# DIFFAMP.net
KiCad netlist of a schematic drawn in Altium Designer
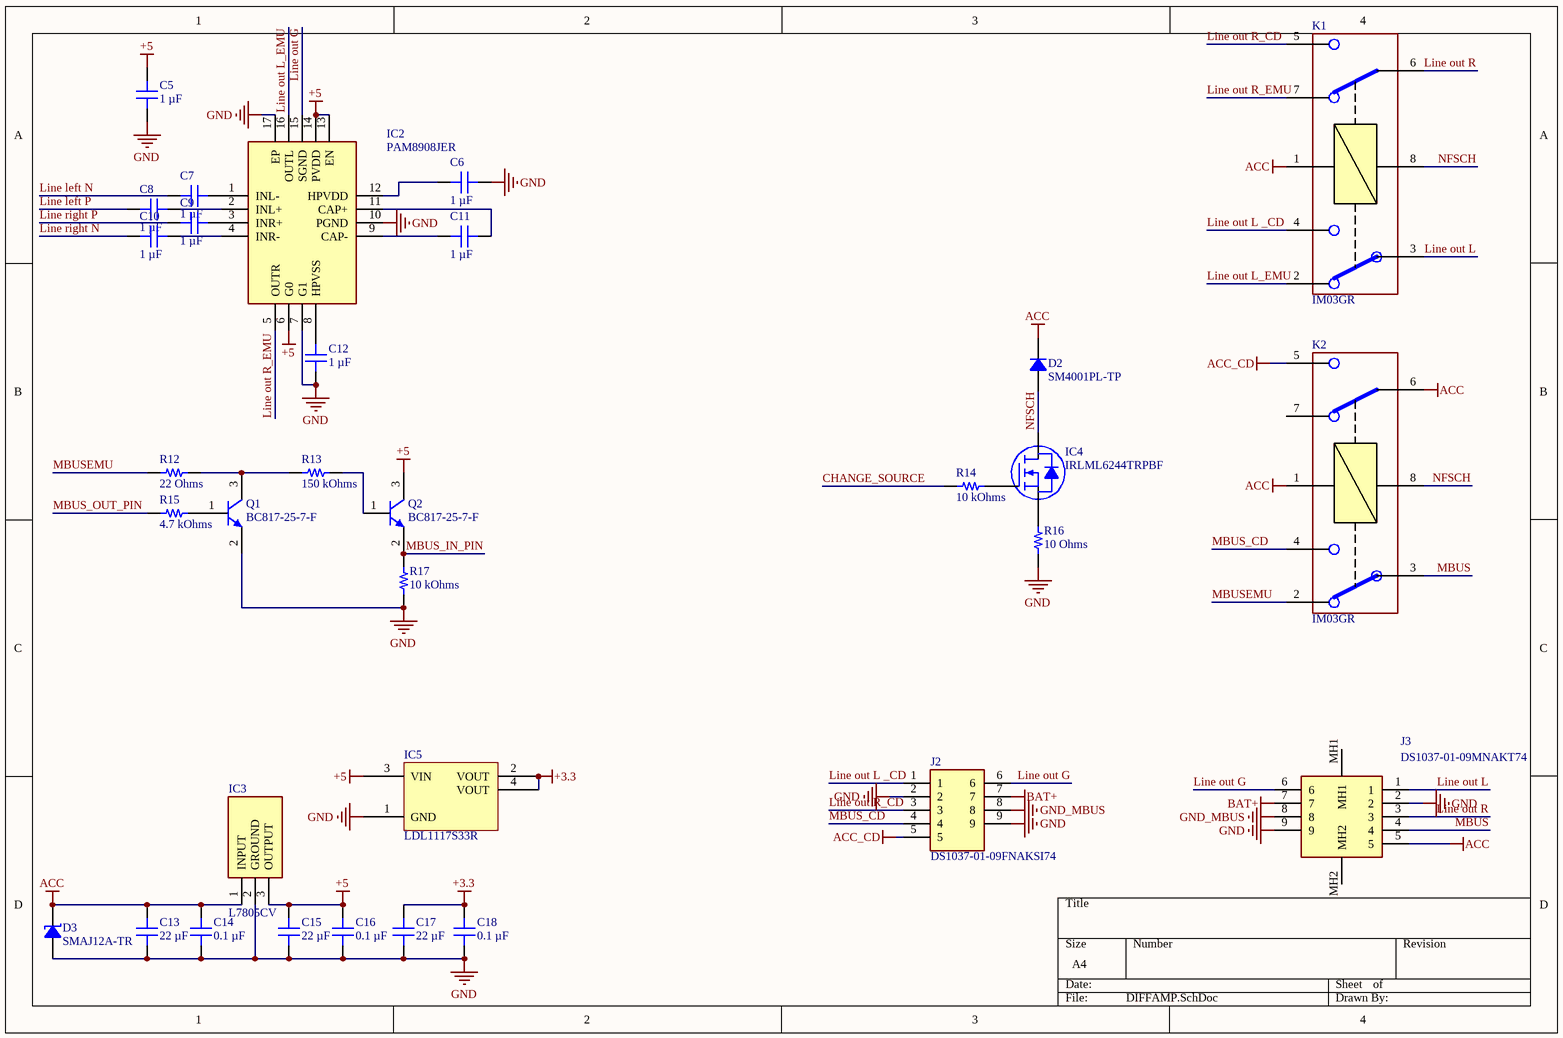
[diagram p0: DIFFAMP.SchDoc]

(export (version "E")
  (design (tool "Eeschema 10.0.6"))
  (components
    (comp (ref "C5")
      (value "1 µF")
      (footprint "CAP 0603_1608")
      (description "CAP CER 1UF 25V X5R 0603")
      (fields (field (name "PART NUMBER") "CC0603KRX5R8BB105") (field (name "MANUFACTURER") "Yageo"))
      (libsource (lib "Celestial Altium Library - altium_library") (part "Capacitor"))
    )
    (comp (ref "C6")
      (value "1 µF")
      (footprint "CAP 0603_1608")
      (description "CAP CER 1UF 25V X5R 0603")
      (fields (field (name "PART NUMBER") "CC0603KRX5R8BB105") (field (name "MANUFACTURER") "Yageo"))
      (libsource (lib "Celestial Altium Library - altium_library") (part "Capacitor"))
    )
    (comp (ref "C7")
      (value "1 µF")
      (footprint "CAP 0603_1608")
      (description "CAP CER 1UF 25V X5R 0603")
      (fields (field (name "PART NUMBER") "CC0603KRX5R8BB105") (field (name "MANUFACTURER") "Yageo"))
      (libsource (lib "Celestial Altium Library - altium_library") (part "Capacitor"))
    )
    (comp (ref "C8")
      (value "1 µF")
      (footprint "CAP 0603_1608")
      (description "CAP CER 1UF 25V X5R 0603")
      (fields (field (name "PART NUMBER") "CC0603KRX5R8BB105") (field (name "MANUFACTURER") "Yageo"))
      (libsource (lib "Celestial Altium Library - altium_library") (part "Capacitor"))
    )
    (comp (ref "C9")
      (value "1 µF")
      (footprint "CAP 0603_1608")
      (description "CAP CER 1UF 25V X5R 0603")
      (fields (field (name "PART NUMBER") "CC0603KRX5R8BB105") (field (name "MANUFACTURER") "Yageo"))
      (libsource (lib "Celestial Altium Library - altium_library") (part "Capacitor"))
    )
    (comp (ref "C10")
      (value "1 µF")
      (footprint "CAP 0603_1608")
      (description "CAP CER 1UF 25V X5R 0603")
      (fields (field (name "PART NUMBER") "CC0603KRX5R8BB105") (field (name "MANUFACTURER") "Yageo"))
      (libsource (lib "Celestial Altium Library - altium_library") (part "Capacitor"))
    )
    (comp (ref "C11")
      (value "1 µF")
      (footprint "CAP 0603_1608")
      (description "CAP CER 1UF 25V X5R 0603")
      (fields (field (name "PART NUMBER") "CC0603KRX5R8BB105") (field (name "MANUFACTURER") "Yageo"))
      (libsource (lib "Celestial Altium Library - altium_library") (part "Capacitor"))
    )
    (comp (ref "C12")
      (value "1 µF")
      (footprint "CAP 0603_1608")
      (description "CAP CER 1UF 25V X5R 0603")
      (fields (field (name "PART NUMBER") "CC0603KRX5R8BB105") (field (name "MANUFACTURER") "Yageo"))
      (libsource (lib "Celestial Altium Library - altium_library") (part "Capacitor"))
    )
    (comp (ref "C13")
      (value "22 µF")
      (footprint "CAP 1206_3216 - 0.8MM")
      (description "CAP CER 22UF 25V X5R 1206")
      (fields (field (name "PART NUMBER") "CC1206MKX5R8BB226") (field (name "MANUFACTURER") "Yageo"))
      (libsource (lib "Celestial Altium Library - altium_library") (part "Capacitor"))
    )
    (comp (ref "C14")
      (value "0.1 µF")
      (footprint "CAP 0603_1608")
      (description "CAP CER 0.1UF 16V X7R 0603")
      (fields (field (name "PART NUMBER") "CC0603KRX7R7BB104") (field (name "MANUFACTURER") "Yageo"))
      (libsource (lib "Celestial Altium Library - altium_library") (part "Capacitor"))
    )
    (comp (ref "C15")
      (value "22 µF")
      (footprint "CAP 1206_3216 - 0.8MM")
      (description "CAP CER 22UF 25V X5R 1206")
      (fields (field (name "PART NUMBER") "CC1206MKX5R8BB226") (field (name "MANUFACTURER") "Yageo"))
      (libsource (lib "Celestial Altium Library - altium_library") (part "Capacitor"))
    )
    (comp (ref "C16")
      (value "0.1 µF")
      (footprint "CAP 0603_1608")
      (description "CAP CER 0.1UF 16V X7R 0603")
      (fields (field (name "PART NUMBER") "CC0603KRX7R7BB104") (field (name "MANUFACTURER") "Yageo"))
      (libsource (lib "Celestial Altium Library - altium_library") (part "Capacitor"))
    )
    (comp (ref "C17")
      (value "22 µF")
      (footprint "CAP 1206_3216 - 0.8MM")
      (description "CAP CER 22UF 25V X5R 1206")
      (fields (field (name "PART NUMBER") "CC1206MKX5R8BB226") (field (name "MANUFACTURER") "Yageo"))
      (libsource (lib "Celestial Altium Library - altium_library") (part "Capacitor"))
    )
    (comp (ref "C18")
      (value "0.1 µF")
      (footprint "CAP 0603_1608")
      (description "CAP CER 0.1UF 16V X7R 0603")
      (fields (field (name "PART NUMBER") "CC0603KRX7R7BB104") (field (name "MANUFACTURER") "Yageo"))
      (libsource (lib "Celestial Altium Library - altium_library") (part "Capacitor"))
    )
    (comp (ref "D2")
      (value "SM4001PL-TP")
      (footprint "SOD123F")
      (description "DIODE GEN PURP 50V 1A SOD123FL")
      (fields (field (name "MANUFACTURER") "Micro Commercial Co"))
      (libsource (lib "Celestial Altium Library - altium_library") (part "Diode"))
    )
    (comp (ref "D3")
      (value "SMAJ12A-TR")
      (footprint "DO214AC SMA")
      (description "TVS DIODE 12VWM 25.3VC SMA")
      (fields (field (name "MANUFACTURER") "STMicroelectronics"))
      (libsource (lib "Celestial Altium Library - altium_library") (part "DIODE TVS UNI"))
    )
    (comp (ref "IC2")
      (value "PAM8908JER")
      (footprint "SamacSys:QFN50P300X300X65-17N")
      (description "Integrated Circuit")
      (fields (field (name "MOUSER PART NUMBER") "621-PAM8908JER"))
      (libsource (lib "*") (part "PAM8908JER"))
    )
    (comp (ref "IC3")
      (value "L7805CV")
      (footprint "SamacSys:TO255P460X1020X2008-3P")
      (description "Integrated Circuit")
      (fields (field (name "MOUSER PART NUMBER") "511-L7805CV"))
      (libsource (lib "SamacSys") (part "L7805CV"))
    )
    (comp (ref "IC4")
      (value "IRLML6244TRPBF")
      (footprint "INFINEON SOT-23-3")
      (description "MOSFET N-CH 20V 6.3A SOT23")
      (fields (field (name "MANUFACTURER") "Infineon Technologies"))
      (libsource (lib "Celestial Altium Library - altium_library") (part "INFINEON MOSFET N-CH SOT-23-3 GSD"))
    )
    (comp (ref "IC5")
      (value "LDL1117S33R")
      (footprint "ST SOT-223")
      (description "IC REG LINEAR 3.3V 1.2A SOT223")
      (fields (field (name "MANUFACTURER") "STMicroelectronics"))
      (libsource (lib "Celestial Altium Library - altium_library") (part "ST LDL1117"))
    )
    (comp (ref "J2")
      (value "DS1037-01-09FNAKSI74")
      (footprint "SamacSys:DS1037-01-09FNAKSI74")
      (description "Connector")
      (libsource (lib "*") (part "DS1037-01-09FNAKSI74"))
    )
    (comp (ref "J3")
      (value "DS1037-01-09MNAKT74")
      (footprint "SamacSys:DS10370109MNAKT74")
      (description "Connector")
      (libsource (lib "*") (part "DS1037-01-09MNAKT74"))
    )
    (comp (ref "K1")
      (value "IM03GR")
      (footprint "SamacSys:IM06GR")
      (description "Relay or Contactor")
      (fields (field (name "MOUSER PART NUMBER") "655-IM03GR"))
      (libsource (lib "SamacSys") (part "IM03GR"))
    )
    (comp (ref "K2")
      (value "IM03GR")
      (footprint "SamacSys:IM06GR")
      (description "Relay or Contactor")
      (fields (field (name "MOUSER PART NUMBER") "655-IM03GR"))
      (libsource (lib "SamacSys") (part "IM03GR"))
    )
    (comp (ref "Q1")
      (value "BC817-25-7-F")
      (footprint "DIODES SOT-23-3")
      (description "TRANS NPN 45V 0.5A SOT23-3")
      (fields (field (name "MANUFACTURER") "Diodes Incorporated"))
      (libsource (lib "Celestial Altium Library - altium_library") (part "DIODES INC NPN SOT-23-3"))
    )
    (comp (ref "Q2")
      (value "BC817-25-7-F")
      (footprint "DIODES SOT-23-3")
      (description "TRANS NPN 45V 0.5A SOT23-3")
      (fields (field (name "MANUFACTURER") "Diodes Incorporated"))
      (libsource (lib "Celestial Altium Library - altium_library") (part "DIODES INC NPN SOT-23-3"))
    )
    (comp (ref "R12")
      (value "22 Ohms")
      (footprint "YAGEO RES 0603_1608")
      (description "RES 22 OHM 5% 1/10W 0603")
      (fields (field (name "PART NUMBER") "RC0603JR-0722RL") (field (name "MANUFACTURER") "Yageo"))
      (libsource (lib "Celestial Altium Library - altium_library") (part "Resistor"))
    )
    (comp (ref "R13")
      (value "150 kOhms")
      (footprint "YAGEO RES 0603_1608")
      (description "RES 150K OHM 1% 1/10W 0603")
      (fields (field (name "PART NUMBER") "RC0603FR-07150KL") (field (name "MANUFACTURER") "Yageo"))
      (libsource (lib "Celestial Altium Library - altium_library") (part "Resistor"))
    )
    (comp (ref "R14")
      (value "10 kOhms")
      (footprint "YAGEO RES 0603_1608")
      (description "RES 10K OHM 1% 1/10W 0603")
      (fields (field (name "PART NUMBER") "RC0603FR-1310KL") (field (name "MANUFACTURER") "Yageo"))
      (libsource (lib "Celestial Altium Library - altium_library") (part "Resistor"))
    )
    (comp (ref "R15")
      (value "4.7 kOhms")
      (footprint "YAGEO RES 0603_1608")
      (description "RES 4.7K OHM 1% 1/10W 0603")
      (fields (field (name "PART NUMBER") "RC0603FR-074K7L") (field (name "MANUFACTURER") "Yageo"))
      (libsource (lib "Celestial Altium Library - altium_library") (part "Resistor"))
    )
    (comp (ref "R16")
      (value "10 Ohms")
      (footprint "YAGEO RES 0603_1608")
      (description "RES 10 OHM 1% 1/10W 0603")
      (fields (field (name "PART NUMBER") "RC0603FR-0710RL") (field (name "MANUFACTURER") "Yageo"))
      (libsource (lib "Celestial Altium Library - altium_library") (part "Resistor"))
    )
    (comp (ref "R17")
      (value "10 kOhms")
      (footprint "YAGEO RES 0603_1608")
      (description "RES 10K OHM 1% 1/10W 0603")
      (fields (field (name "PART NUMBER") "RC0603FR-1310KL") (field (name "MANUFACTURER") "Yageo"))
      (libsource (lib "Celestial Altium Library - altium_library") (part "Resistor"))
    )
  )
  (nets
    (net (code "1") (name "+3.3") (class "Default")
      (node (ref "C17") (pin "2") (pinfunction "2_2") (pintype "passive"))
      (node (ref "C18") (pin "2") (pinfunction "2_2") (pintype "passive"))
      (node (ref "IC5") (pin "2") (pinfunction "VOUT_2") (pintype "passive"))
      (node (ref "IC5") (pin "4") (pinfunction "VOUT_4") (pintype "passive"))
    )
    (net (code "2") (name "+5") (class "Default")
      (node (ref "C15") (pin "2") (pinfunction "2_2") (pintype "passive"))
      (node (ref "C16") (pin "2") (pinfunction "2_2") (pintype "passive"))
      (node (ref "C5") (pin "2") (pinfunction "2_2") (pintype "passive"))
      (node (ref "IC2") (pin "13") (pinfunction "EN_13") (pintype "passive"))
      (node (ref "IC2") (pin "14") (pinfunction "PVDD_14") (pintype "passive"))
      (node (ref "IC2") (pin "6") (pinfunction "G0_6") (pintype "passive"))
      (node (ref "IC3") (pin "3") (pinfunction "OUTPUT_3") (pintype "passive"))
      (node (ref "IC5") (pin "3") (pinfunction "VIN_3") (pintype "passive"))
      (node (ref "Q2") (pin "3") (pinfunction "C_3") (pintype "passive"))
    )
    (net (code "3") (name "/CHANGE_SOURCE") (class "Default")
      (node (ref "R14") (pin "1") (pinfunction "1_1") (pintype "passive"))
    )
    (net (code "4") (name "/Line left N") (class "Default")
      (node (ref "C7") (pin "1") (pinfunction "1_1") (pintype "passive"))
    )
    (net (code "5") (name "/Line left P") (class "Default")
      (node (ref "C8") (pin "1") (pinfunction "1_1") (pintype "passive"))
    )
    (net (code "6") (name "/Line out G") (class "Default")
      (node (ref "IC2") (pin "15") (pinfunction "SGND_15") (pintype "passive"))
      (node (ref "J2") (pin "6") (pinfunction "6_6") (pintype "passive"))
      (node (ref "J3") (pin "6") (pinfunction "6_6") (pintype "passive"))
    )
    (net (code "7") (name "/Line out L") (class "Default")
      (node (ref "J3") (pin "1") (pinfunction "1_1") (pintype "passive"))
      (node (ref "K1") (pin "3") (pinfunction "3_3") (pintype "passive"))
    )
    (net (code "8") (name "/Line out L _CD") (class "Default")
      (node (ref "J2") (pin "1") (pinfunction "1_1") (pintype "passive"))
      (node (ref "K1") (pin "4") (pinfunction "4_4") (pintype "passive"))
    )
    (net (code "9") (name "/Line out L_EMU") (class "Default")
      (node (ref "IC2") (pin "16") (pinfunction "OUTL_16") (pintype "passive"))
      (node (ref "K1") (pin "2") (pinfunction "2_2") (pintype "passive"))
    )
    (net (code "10") (name "/Line out R") (class "Default")
      (node (ref "J3") (pin "3") (pinfunction "3_3") (pintype "passive"))
      (node (ref "K1") (pin "6") (pinfunction "6_6") (pintype "passive"))
    )
    (net (code "11") (name "/Line out R_CD") (class "Default")
      (node (ref "J2") (pin "3") (pinfunction "3_3") (pintype "passive"))
      (node (ref "K1") (pin "5") (pinfunction "5_5") (pintype "passive"))
    )
    (net (code "12") (name "/Line out R_EMU") (class "Default")
      (node (ref "IC2") (pin "5") (pinfunction "OUTR_5") (pintype "passive"))
      (node (ref "K1") (pin "7") (pinfunction "7_7") (pintype "passive"))
    )
    (net (code "13") (name "/Line right N") (class "Default")
      (node (ref "C10") (pin "1") (pinfunction "1_1") (pintype "passive"))
    )
    (net (code "14") (name "/Line right P") (class "Default")
      (node (ref "C9") (pin "1") (pinfunction "1_1") (pintype "passive"))
    )
    (net (code "15") (name "/MBUS") (class "Default")
      (node (ref "J3") (pin "4") (pinfunction "4_4") (pintype "passive"))
      (node (ref "K2") (pin "3") (pinfunction "3_3") (pintype "passive"))
    )
    (net (code "16") (name "/MBUSEMU") (class "Default")
      (node (ref "K2") (pin "2") (pinfunction "2_2") (pintype "passive"))
      (node (ref "R12") (pin "1") (pinfunction "1_1") (pintype "passive"))
    )
    (net (code "17") (name "/MBUS_CD") (class "Default")
      (node (ref "J2") (pin "4") (pinfunction "4_4") (pintype "passive"))
      (node (ref "K2") (pin "4") (pinfunction "4_4") (pintype "passive"))
    )
    (net (code "18") (name "/MBUS_IN_PIN") (class "Default")
      (node (ref "Q2") (pin "2") (pinfunction "E_2") (pintype "passive"))
      (node (ref "R17") (pin "2") (pinfunction "2_2") (pintype "passive"))
    )
    (net (code "19") (name "/MBUS_OUT_PIN") (class "Default")
      (node (ref "R15") (pin "1") (pinfunction "1_1") (pintype "passive"))
    )
    (net (code "20") (name "/NFSCH") (class "Default")
      (node (ref "D2") (pin "1") (pinfunction "1_1") (pintype "passive"))
      (node (ref "IC4") (pin "3") (pinfunction "D_3") (pintype "passive"))
      (node (ref "K1") (pin "8") (pinfunction "8_8") (pintype "passive"))
      (node (ref "K2") (pin "8") (pinfunction "8_8") (pintype "passive"))
    )
    (net (code "21") (name "ACC") (class "Default")
      (node (ref "C13") (pin "2") (pinfunction "2_2") (pintype "passive"))
      (node (ref "C14") (pin "2") (pinfunction "2_2") (pintype "passive"))
      (node (ref "D2") (pin "2") (pinfunction "2_2") (pintype "passive"))
      (node (ref "D3") (pin "2") (pinfunction "2_2") (pintype "passive"))
      (node (ref "IC3") (pin "1") (pinfunction "INPUT_1") (pintype "passive"))
      (node (ref "J3") (pin "5") (pinfunction "5_5") (pintype "passive"))
      (node (ref "K1") (pin "1") (pinfunction "1_1") (pintype "passive"))
      (node (ref "K2") (pin "1") (pinfunction "1_1") (pintype "passive"))
      (node (ref "K2") (pin "6") (pinfunction "6_6") (pintype "passive"))
    )
    (net (code "22") (name "ACC_CD") (class "Default")
      (node (ref "J2") (pin "5") (pinfunction "5_5") (pintype "passive"))
      (node (ref "K2") (pin "5") (pinfunction "5_5") (pintype "passive"))
    )
    (net (code "23") (name "BAT+") (class "Default")
      (node (ref "J2") (pin "7") (pinfunction "7_7") (pintype "passive"))
      (node (ref "J3") (pin "7") (pinfunction "7_7") (pintype "passive"))
    )
    (net (code "24") (name "GND") (class "Default")
      (node (ref "C12") (pin "1") (pinfunction "1_1") (pintype "passive"))
      (node (ref "C13") (pin "1") (pinfunction "1_1") (pintype "passive"))
      (node (ref "C14") (pin "1") (pinfunction "1_1") (pintype "passive"))
      (node (ref "C15") (pin "1") (pinfunction "1_1") (pintype "passive"))
      (node (ref "C16") (pin "1") (pinfunction "1_1") (pintype "passive"))
      (node (ref "C17") (pin "1") (pinfunction "1_1") (pintype "passive"))
      (node (ref "C18") (pin "1") (pinfunction "1_1") (pintype "passive"))
      (node (ref "C5") (pin "1") (pinfunction "1_1") (pintype "passive"))
      (node (ref "C6") (pin "2") (pinfunction "2_2") (pintype "passive"))
      (node (ref "D3") (pin "1") (pinfunction "1_1") (pintype "passive"))
      (node (ref "IC2") (pin "10") (pinfunction "PGND_10") (pintype "passive"))
      (node (ref "IC2") (pin "17") (pinfunction "EP_17") (pintype "passive"))
      (node (ref "IC2") (pin "7") (pinfunction "G1_7") (pintype "passive"))
      (node (ref "IC3") (pin "2") (pinfunction "GROUND_2") (pintype "passive"))
      (node (ref "IC5") (pin "1") (pinfunction "GND_1") (pintype "passive"))
      (node (ref "J2") (pin "2") (pinfunction "2_2") (pintype "passive"))
      (node (ref "J2") (pin "9") (pinfunction "9_9") (pintype "passive"))
      (node (ref "J3") (pin "2") (pinfunction "2_2") (pintype "passive"))
      (node (ref "J3") (pin "9") (pinfunction "9_9") (pintype "passive"))
      (node (ref "Q1") (pin "2") (pinfunction "E_2") (pintype "passive"))
      (node (ref "R16") (pin "1") (pinfunction "1_1") (pintype "passive"))
      (node (ref "R17") (pin "1") (pinfunction "1_1") (pintype "passive"))
    )
    (net (code "25") (name "GND_MBUS") (class "Default")
      (node (ref "J2") (pin "8") (pinfunction "8_8") (pintype "passive"))
      (node (ref "J3") (pin "8") (pinfunction "8_8") (pintype "passive"))
    )
    (net (code "26") (name "Net-(IC2-CAP+)") (class "Default")
      (node (ref "C11") (pin "2") (pinfunction "2_2") (pintype "passive"))
      (node (ref "IC2") (pin "11") (pinfunction "CAP+_11") (pintype "passive"))
    )
    (net (code "27") (name "Net-(IC2-CAP-)") (class "Default")
      (node (ref "C11") (pin "1") (pinfunction "1_1") (pintype "passive"))
      (node (ref "IC2") (pin "9") (pinfunction "CAP-_9") (pintype "passive"))
    )
    (net (code "28") (name "Net-(IC2-HPVDD)") (class "Default")
      (node (ref "C6") (pin "1") (pinfunction "1_1") (pintype "passive"))
      (node (ref "IC2") (pin "12") (pinfunction "HPVDD_12") (pintype "passive"))
    )
    (net (code "29") (name "Net-(IC2-HPVSS)") (class "Default")
      (node (ref "C12") (pin "2") (pinfunction "2_2") (pintype "passive"))
      (node (ref "IC2") (pin "8") (pinfunction "HPVSS_8") (pintype "passive"))
    )
    (net (code "30") (name "Net-(IC2-INL+)") (class "Default")
      (node (ref "C8") (pin "2") (pinfunction "2_2") (pintype "passive"))
      (node (ref "IC2") (pin "2") (pinfunction "INL+_2") (pintype "passive"))
    )
    (net (code "31") (name "Net-(IC2-INL-)") (class "Default")
      (node (ref "C7") (pin "2") (pinfunction "2_2") (pintype "passive"))
      (node (ref "IC2") (pin "1") (pinfunction "INL-_1") (pintype "passive"))
    )
    (net (code "32") (name "Net-(IC2-INR+)") (class "Default")
      (node (ref "C9") (pin "2") (pinfunction "2_2") (pintype "passive"))
      (node (ref "IC2") (pin "3") (pinfunction "INR+_3") (pintype "passive"))
    )
    (net (code "33") (name "Net-(IC2-INR-)") (class "Default")
      (node (ref "C10") (pin "2") (pinfunction "2_2") (pintype "passive"))
      (node (ref "IC2") (pin "4") (pinfunction "INR-_4") (pintype "passive"))
    )
    (net (code "34") (name "Net-(IC4-G)") (class "Default")
      (node (ref "IC4") (pin "1") (pinfunction "G_1") (pintype "passive"))
      (node (ref "R14") (pin "2") (pinfunction "2_2") (pintype "passive"))
    )
    (net (code "35") (name "Net-(IC4-S)") (class "Default")
      (node (ref "IC4") (pin "2") (pinfunction "S_2") (pintype "passive"))
      (node (ref "R16") (pin "2") (pinfunction "2_2") (pintype "passive"))
    )
    (net (code "36") (name "Net-(Q1-B)") (class "Default")
      (node (ref "Q1") (pin "1") (pinfunction "B_1") (pintype "passive"))
      (node (ref "R15") (pin "2") (pinfunction "2_2") (pintype "passive"))
    )
    (net (code "37") (name "Net-(Q1-C)") (class "Default")
      (node (ref "Q1") (pin "3") (pinfunction "C_3") (pintype "passive"))
      (node (ref "R12") (pin "2") (pinfunction "2_2") (pintype "passive"))
      (node (ref "R13") (pin "1") (pinfunction "1_1") (pintype "passive"))
    )
    (net (code "38") (name "Net-(Q2-B)") (class "Default")
      (node (ref "Q2") (pin "1") (pinfunction "B_1") (pintype "passive"))
      (node (ref "R13") (pin "2") (pinfunction "2_2") (pintype "passive"))
    )
    (net (code "39") (name "unconnected-(J3-PadMH1)") (class "Default")
      (node (ref "J3") (pin "MH1") (pinfunction "MH1_MH1") (pintype "passive"))
    )
    (net (code "40") (name "unconnected-(J3-PadMH2)") (class "Default")
      (node (ref "J3") (pin "MH2") (pinfunction "MH2_MH2") (pintype "passive"))
    )
    (net (code "41") (name "unconnected-(K2-Pad7)") (class "Default")
      (node (ref "K2") (pin "7") (pinfunction "7_7") (pintype "passive"))
    )
  )
)
